# LEDs.net
KiCad netlist of a schematic drawn in EAGLE
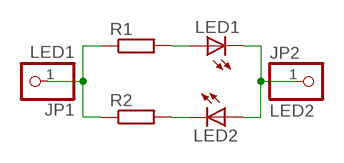
[diagram p0: schematic, sheet 1]

(export (version "E")
  (design (tool "Eeschema 10.0.6"))
  (components
    (comp (ref "JP1")
      (value "LED1")
      (footprint "eagle-import:1X01")
      (libsource (lib "eagle-import") (part "PINHD-1X1"))
    )
    (comp (ref "JP2")
      (value "LED2")
      (footprint "eagle-import:1X01")
      (libsource (lib "eagle-import") (part "PINHD-1X1"))
    )
    (comp (ref "LED1")
      (value "LED3MM")
      (footprint "eagle-import:LED3MM")
      (libsource (lib "eagle-import") (part "LED3MM"))
    )
    (comp (ref "LED2")
      (value "LED3MM")
      (footprint "eagle-import:LED3MM")
      (libsource (lib "eagle-import") (part "LED3MM"))
    )
    (comp (ref "R1")
      (value "R-EU_0204/2V")
      (footprint "eagle-import:0204V")
      (libsource (lib "eagle-import") (part "R-EU_0204/2V"))
    )
    (comp (ref "R2")
      (value "R-EU_0204/2V")
      (footprint "eagle-import:0204V")
      (libsource (lib "eagle-import") (part "R-EU_0204/2V"))
    )
  )
  (nets
    (net (code "1") (name "Net-(JP1-Pad1)") (class "Default")
      (node (ref "JP1") (pin "1") (pinfunction "1_1") (pintype "passive"))
      (node (ref "R1") (pin "1") (pinfunction "1_1") (pintype "passive"))
      (node (ref "R2") (pin "1") (pinfunction "1_1") (pintype "passive"))
    )
    (net (code "2") (name "Net-(LED1-C)") (class "Default")
      (node (ref "JP2") (pin "1") (pinfunction "1_1") (pintype "passive"))
      (node (ref "LED1") (pin "K") (pinfunction "C_K") (pintype "passive"))
      (node (ref "LED2") (pin "A") (pinfunction "A_A") (pintype "passive"))
    )
    (net (code "3") (name "Net-(LED1-PadA)") (class "Default")
      (node (ref "LED1") (pin "A") (pinfunction "A_A") (pintype "passive"))
      (node (ref "R1") (pin "2") (pinfunction "2_2") (pintype "passive"))
    )
    (net (code "4") (name "Net-(LED2-C)") (class "Default")
      (node (ref "LED2") (pin "K") (pinfunction "C_K") (pintype "passive"))
      (node (ref "R2") (pin "2") (pinfunction "2_2") (pintype "passive"))
    )
  )
)
